# Support.net
KiCad netlist of a schematic drawn in Altium Designer
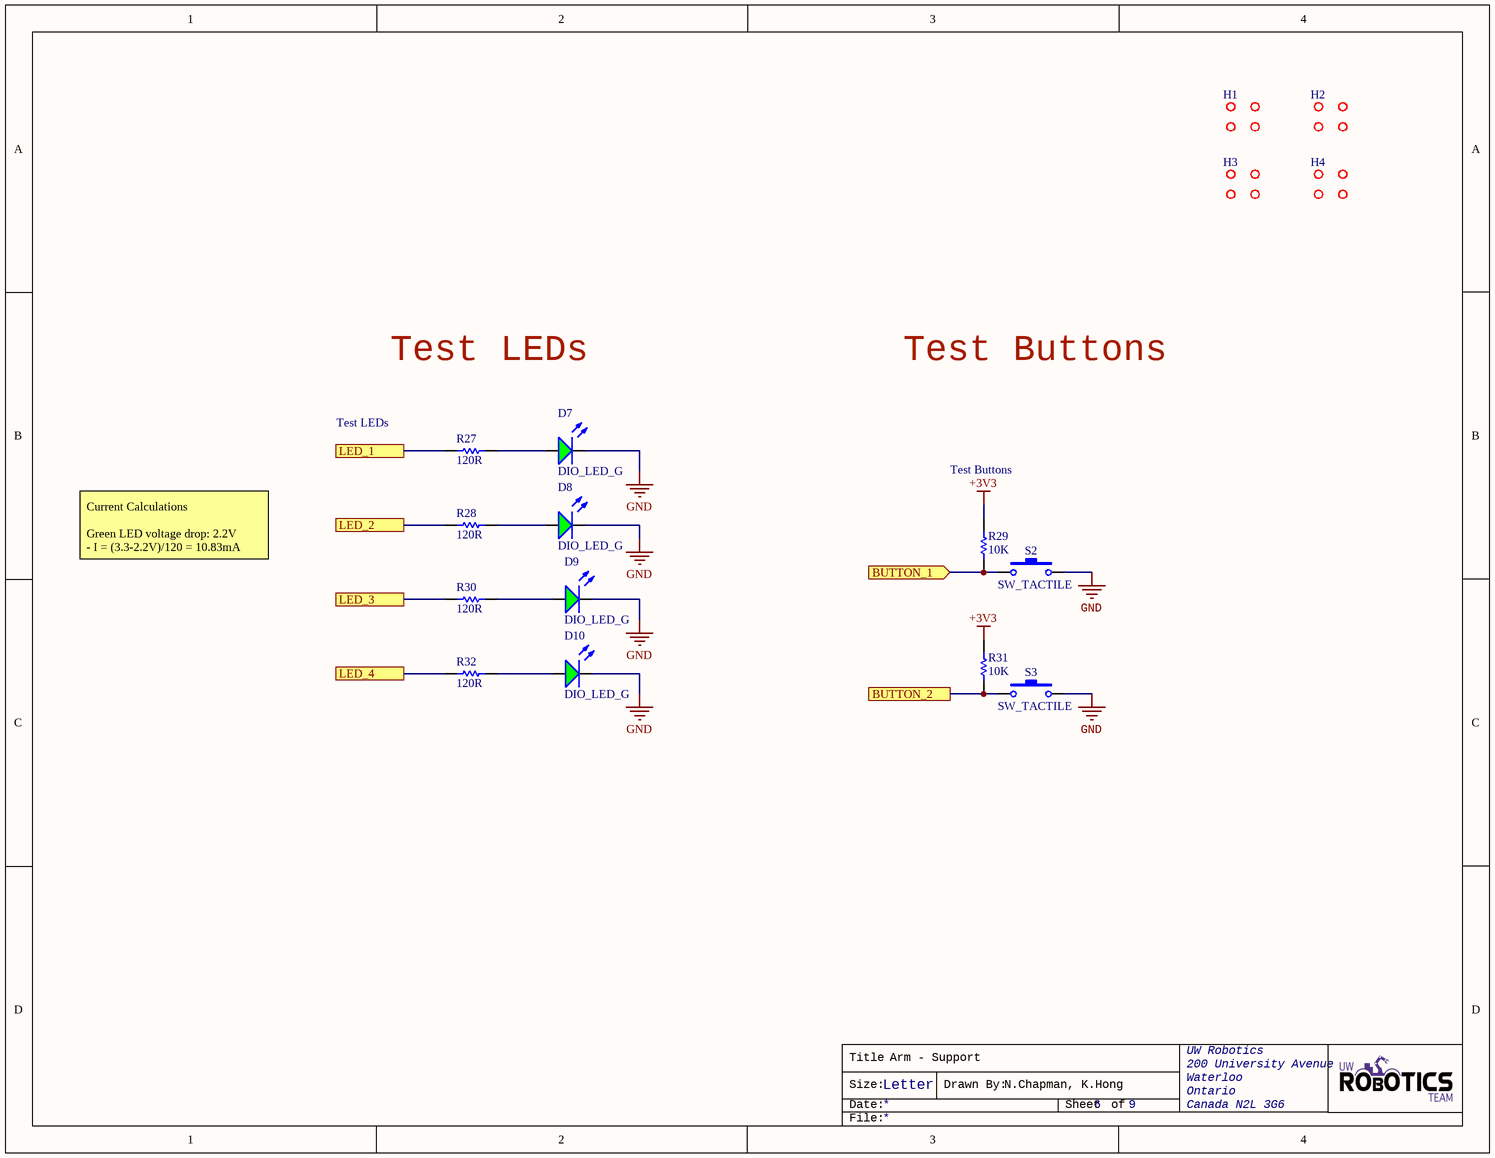
[diagram p0: Support.SchDoc]

(export (version "E")
  (design (tool "Eeschema 10.0.6"))
  (components
    (comp (ref "D7")
      (value "DIO_LED_G")
      (footprint "LED_0805_LINE")
      (description "LED GREEN DIFFUSED 0805 SMD")
      (fields (field (name "MANUFACTURER") "OSRAM") (field (name "MPN") "LG R971-KN-1"))
      (libsource (lib "UWRT_Schematic_Library_2020") (part "DIO_LED_G"))
    )
    (comp (ref "D8")
      (value "DIO_LED_G")
      (footprint "LED_0805_LINE")
      (description "LED GREEN DIFFUSED 0805 SMD")
      (fields (field (name "MANUFACTURER") "OSRAM") (field (name "MPN") "LG R971-KN-1"))
      (libsource (lib "UWRT_Schematic_Library_2020") (part "DIO_LED_G"))
    )
    (comp (ref "D9")
      (value "DIO_LED_G")
      (footprint "LED_0805_LINE")
      (description "LED GREEN DIFFUSED 0805 SMD")
      (fields (field (name "MANUFACTURER") "OSRAM") (field (name "MPN") "LG R971-KN-1"))
      (libsource (lib "UWRT_Schematic_Library_2020") (part "DIO_LED_G"))
    )
    (comp (ref "D10")
      (value "DIO_LED_G")
      (footprint "LED_0805_LINE")
      (description "LED GREEN DIFFUSED 0805 SMD")
      (fields (field (name "MANUFACTURER") "OSRAM") (field (name "MPN") "LG R971-KN-1"))
      (libsource (lib "UWRT_Schematic_Library_2020") (part "DIO_LED_G"))
    )
    (comp (ref "H1")
      (value "MOUNTING_HOLES")
      (footprint "MOUNTING_HOLE")
      (description "6cm x 6cm")
      (libsource (lib "UWRT_Schematic_Library_2020") (part "MOUNTING_HOLES"))
    )
    (comp (ref "H2")
      (value "MOUNTING_HOLES")
      (footprint "MOUNTING_HOLE")
      (description "6cm x 6cm")
      (libsource (lib "UWRT_Schematic_Library_2020") (part "MOUNTING_HOLES"))
    )
    (comp (ref "H3")
      (value "MOUNTING_HOLES")
      (footprint "MOUNTING_HOLE")
      (description "6cm x 6cm")
      (libsource (lib "UWRT_Schematic_Library_2020") (part "MOUNTING_HOLES"))
    )
    (comp (ref "H4")
      (value "MOUNTING_HOLES")
      (footprint "MOUNTING_HOLE")
      (description "6cm x 6cm")
      (libsource (lib "UWRT_Schematic_Library_2020") (part "MOUNTING_HOLES"))
    )
    (comp (ref "R27")
      (value "120R")
      (footprint "RESC0603(1608)_N")
      (description "RES SMD 120 OHM 5% 1/10W 0603")
      (fields (field (name "MANUFACTURER") "Yageo") (field (name "MPN") "RC0603JR-07120RL"))
      (libsource (lib "UWRT_Schematic_Library_2020") (part "RES_120R_0603"))
    )
    (comp (ref "R28")
      (value "120R")
      (footprint "RESC0603(1608)_N")
      (description "RES SMD 120 OHM 5% 1/10W 0603")
      (fields (field (name "MANUFACTURER") "Yageo") (field (name "MPN") "RC0603JR-07120RL"))
      (libsource (lib "UWRT_Schematic_Library_2020") (part "RES_120R_0603"))
    )
    (comp (ref "R29")
      (value "10K")
      (footprint "RESC0603(1608)_N")
      (description "RES SMD 10K OHM 5% 1/10W 0603")
      (fields (field (name "MANUFACTURER") "Yageo") (field (name "MPN") "RC0603JR-0710KL"))
      (libsource (lib "UWRT_Schematic_Library_2020") (part "RES_10K_0603"))
    )
    (comp (ref "R30")
      (value "120R")
      (footprint "RESC0603(1608)_N")
      (description "RES SMD 120 OHM 5% 1/10W 0603")
      (fields (field (name "MANUFACTURER") "Yageo") (field (name "MPN") "RC0603JR-07120RL"))
      (libsource (lib "UWRT_Schematic_Library_2020") (part "RES_120R_0603"))
    )
    (comp (ref "R31")
      (value "10K")
      (footprint "RESC0603(1608)_N")
      (description "RES SMD 10K OHM 5% 1/10W 0603")
      (fields (field (name "MANUFACTURER") "Yageo") (field (name "MPN") "RC0603JR-0710KL"))
      (libsource (lib "UWRT_Schematic_Library_2020") (part "RES_10K_0603"))
    )
    (comp (ref "R32")
      (value "120R")
      (footprint "RESC0603(1608)_N")
      (description "RES SMD 120 OHM 5% 1/10W 0603")
      (fields (field (name "MANUFACTURER") "Yageo") (field (name "MPN") "RC0603JR-07120RL"))
      (libsource (lib "UWRT_Schematic_Library_2020") (part "RES_120R_0603"))
    )
    (comp (ref "S2")
      (value "SW_TACTILE")
      (footprint "B3U-1100P")
      (description "Tactile Switch (Grey)")
      (fields (field (name "MPN") "B3U-1100P") (field (name "MANUFACTURER") "Omron Electronics Inc-EMC Div"))
      (libsource (lib "UWRT_Schematic_Library_2020") (part "SW_TACTILE"))
    )
    (comp (ref "S3")
      (value "SW_TACTILE")
      (footprint "B3U-1100P")
      (description "Tactile Switch (Grey)")
      (fields (field (name "MPN") "B3U-1100P") (field (name "MANUFACTURER") "Omron Electronics Inc-EMC Div"))
      (libsource (lib "UWRT_Schematic_Library_2020") (part "SW_TACTILE"))
    )
  )
  (nets
    (net (code "1") (name "+3V3") (class "Default")
      (node (ref "R29") (pin "2") (pinfunction "2_2") (pintype "passive"))
      (node (ref "R31") (pin "2") (pinfunction "2_2") (pintype "passive"))
    )
    (net (code "2") (name "/BUTTON_1") (class "Default")
      (node (ref "R29") (pin "1") (pinfunction "1_1") (pintype "passive"))
      (node (ref "S2") (pin "1") (pinfunction "1_1") (pintype "passive"))
    )
    (net (code "3") (name "/BUTTON_2") (class "Default")
      (node (ref "R31") (pin "1") (pinfunction "1_1") (pintype "passive"))
      (node (ref "S3") (pin "1") (pinfunction "1_1") (pintype "passive"))
    )
    (net (code "4") (name "/LED_1") (class "Default")
      (node (ref "R27") (pin "1") (pinfunction "1_1") (pintype "passive"))
    )
    (net (code "5") (name "/LED_2") (class "Default")
      (node (ref "R28") (pin "1") (pinfunction "1_1") (pintype "passive"))
    )
    (net (code "6") (name "/LED_3") (class "Default")
      (node (ref "R30") (pin "1") (pinfunction "1_1") (pintype "passive"))
    )
    (net (code "7") (name "/LED_4") (class "Default")
      (node (ref "R32") (pin "1") (pinfunction "1_1") (pintype "passive"))
    )
    (net (code "8") (name "GND") (class "Default")
      (node (ref "D10") (pin "2") (pinfunction "K_2") (pintype "passive"))
      (node (ref "D7") (pin "2") (pinfunction "K_2") (pintype "passive"))
      (node (ref "D8") (pin "2") (pinfunction "K_2") (pintype "passive"))
      (node (ref "D9") (pin "2") (pinfunction "K_2") (pintype "passive"))
      (node (ref "S2") (pin "2") (pinfunction "2_2") (pintype "passive"))
      (node (ref "S3") (pin "2") (pinfunction "2_2") (pintype "passive"))
    )
    (net (code "9") (name "Net-(D7-A)") (class "Default")
      (node (ref "D7") (pin "1") (pinfunction "A_1") (pintype "passive"))
      (node (ref "R27") (pin "2") (pinfunction "2_2") (pintype "passive"))
    )
    (net (code "10") (name "Net-(D8-A)") (class "Default")
      (node (ref "D8") (pin "1") (pinfunction "A_1") (pintype "passive"))
      (node (ref "R28") (pin "2") (pinfunction "2_2") (pintype "passive"))
    )
    (net (code "11") (name "Net-(D9-A)") (class "Default")
      (node (ref "D9") (pin "1") (pinfunction "A_1") (pintype "passive"))
      (node (ref "R30") (pin "2") (pinfunction "2_2") (pintype "passive"))
    )
    (net (code "12") (name "Net-(D10-A)") (class "Default")
      (node (ref "D10") (pin "1") (pinfunction "A_1") (pintype "passive"))
      (node (ref "R32") (pin "2") (pinfunction "2_2") (pintype "passive"))
    )
  )
)
